# ClockGenerator.net
KiCad netlist of a schematic drawn in Altium Designer
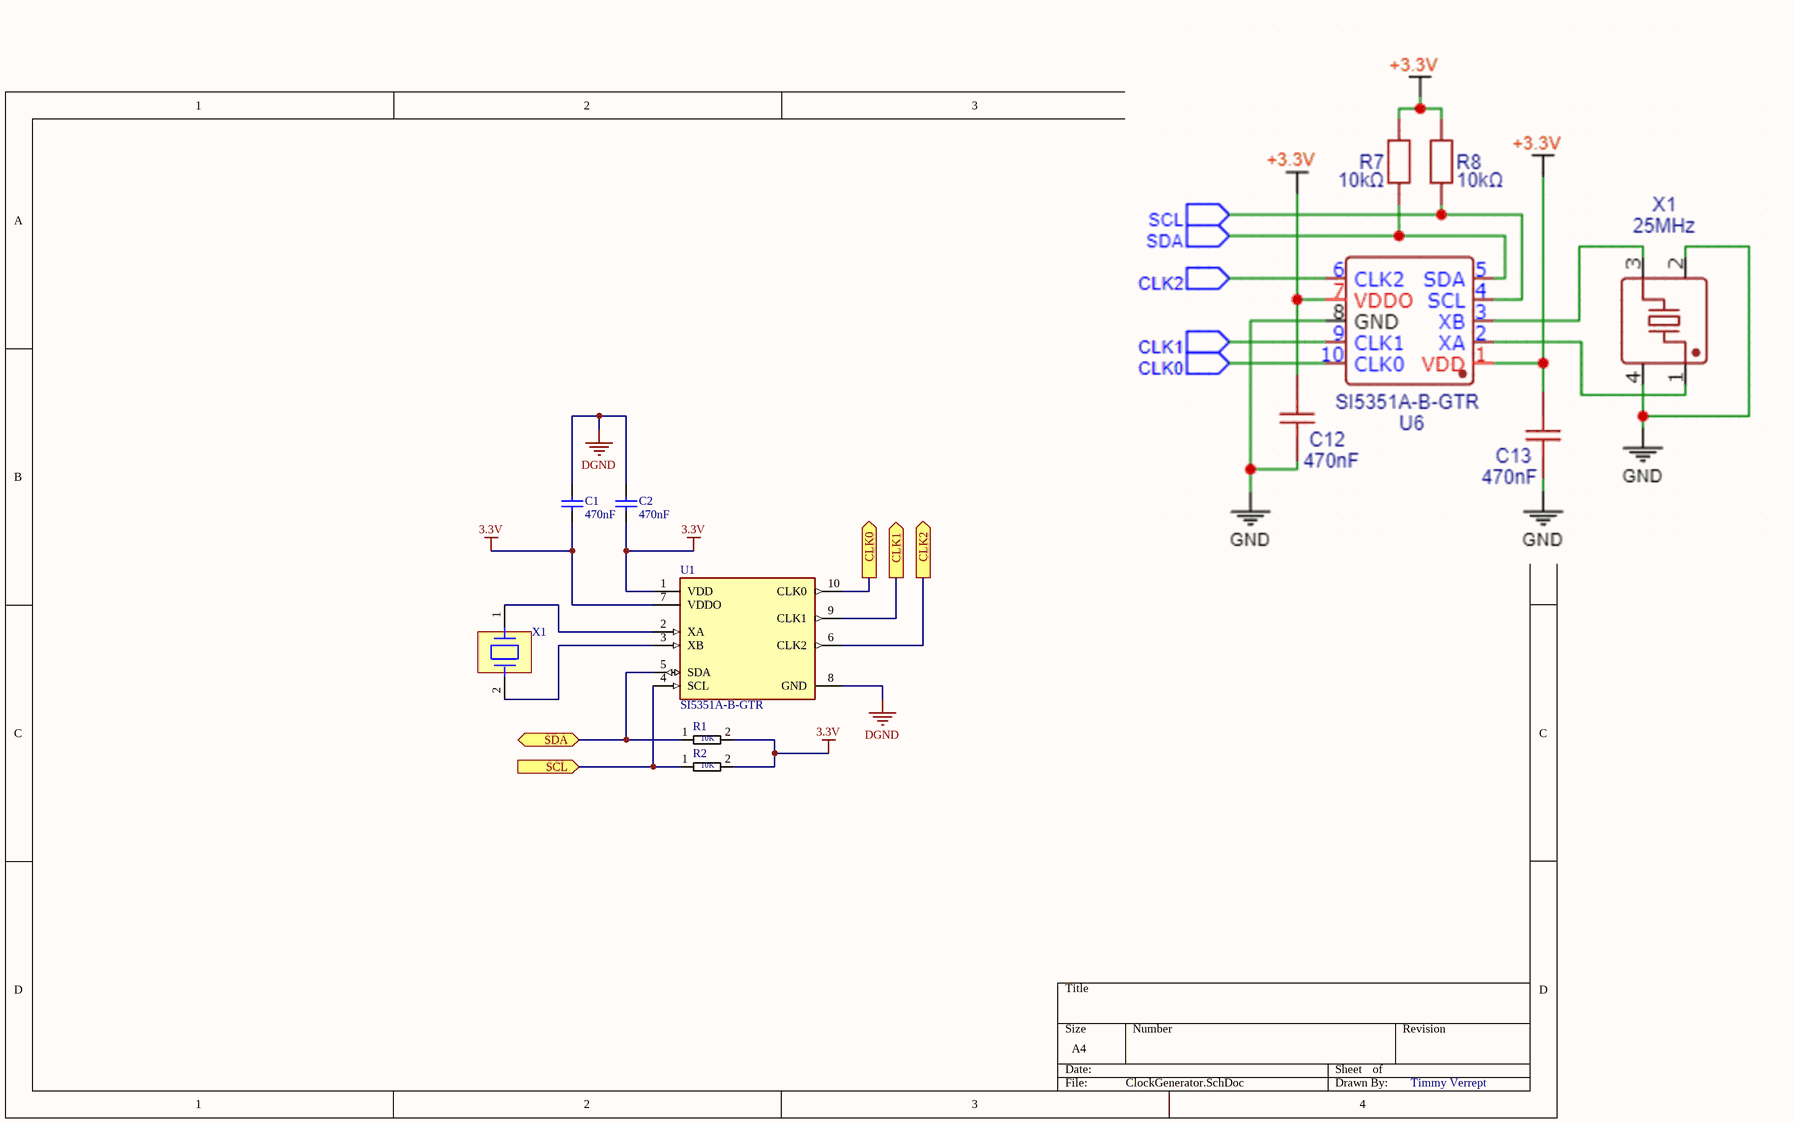
[diagram p0: ClockGenerator.SchDoc]

(export (version "E")
  (design (tool "Eeschema 10.0.6"))
  (components
    (comp (ref "C1")
      (value "470nF")
      (footprint "SMD_CAPACITOR")
      (fields (field (name "MANUFACTURER") "Vitramon") (field (name "PART NUMBER") "VJ0805Y682KXAMT"))
      (libsource (lib "Winnetrie_library") (part "CER Capacitor"))
    )
    (comp (ref "C2")
      (value "470nF")
      (footprint "SMD_CAPACITOR")
      (fields (field (name "MANUFACTURER") "Vitramon") (field (name "PART NUMBER") "VJ0805Y682KXAMT"))
      (libsource (lib "Winnetrie_library") (part "CER Capacitor"))
    )
    (comp (ref "R1")
      (value "10K")
      (footprint "SMD_RESISTOR")
      (description "RES SMD 681 OHM 0.1% 1/8W 0805")
      (fields
        (field (name "MANUFACTURER") "Yageo")
        (field (name "MANUFACTURER PART NUMBER") "RT0805BRD07681RL")
      )
      (libsource (lib "Winnetrie_library") (part "Resistor"))
    )
    (comp (ref "R2")
      (value "10K")
      (footprint "SMD_RESISTOR")
      (description "RES SMD 681 OHM 0.1% 1/8W 0805")
      (fields
        (field (name "MANUFACTURER") "Yageo")
        (field (name "MANUFACTURER PART NUMBER") "RT0805BRD07681RL")
      )
      (libsource (lib "Winnetrie_library") (part "Resistor"))
    )
    (comp (ref "U1")
      (value "SI5351A-B-GTR")
      (footprint "ClockGenerator")
      (description "IC CLK GENERATOR 200MHZ 10MSOP")
      (libsource (lib "Winnetrie_library") (part "Clock Generator"))
    )
    (comp (ref "X1")
      (value "ABM8W-25.0000MHZ-8-D1X-T3")
      (footprint "Crystal")
      (description "Crystal 25.0000Mhz 8Pf Smd Rohs Compliant: Yes ¦Abracon ABM8W-25.0000MHZ-8-D1X-T3")
      (fields
        (field (name "MOUSER PART NUMBER") "815-8W25-8D1XT")
        (field (name "DIGIKEY PART NUMBER") "535-14059-1-ND")
      )
      (libsource (lib "Winnetrie_library") (part "Crystal"))
    )
  )
  (nets
    (net (code "1") (name "/CLK0") (class "Default")
      (node (ref "U1") (pin "10") (pinfunction "CLK0_10") (pintype "output"))
    )
    (net (code "2") (name "/CLK1") (class "Default")
      (node (ref "U1") (pin "9") (pinfunction "CLK1_9") (pintype "output"))
    )
    (net (code "3") (name "/CLK2") (class "Default")
      (node (ref "U1") (pin "6") (pinfunction "CLK2_6") (pintype "output"))
    )
    (net (code "4") (name "/SCL") (class "Default")
      (node (ref "R2") (pin "1") (pinfunction "1_1") (pintype "passive"))
      (node (ref "U1") (pin "4") (pinfunction "SCL_4") (pintype "input"))
    )
    (net (code "5") (name "/SDA") (class "Default")
      (node (ref "R1") (pin "1") (pinfunction "1_1") (pintype "passive"))
      (node (ref "U1") (pin "5") (pinfunction "SDA_5") (pintype "bidirectional"))
    )
    (net (code "6") (name "3.3V") (class "Default")
      (node (ref "C1") (pin "1") (pinfunction "1_1") (pintype "passive"))
      (node (ref "C2") (pin "1") (pinfunction "1_1") (pintype "passive"))
      (node (ref "R1") (pin "2") (pinfunction "2_2") (pintype "passive"))
      (node (ref "R2") (pin "2") (pinfunction "2_2") (pintype "passive"))
      (node (ref "U1") (pin "1") (pinfunction "VDD_1") (pintype "power_in"))
      (node (ref "U1") (pin "7") (pinfunction "VDDO_7") (pintype "power_in"))
    )
    (net (code "7") (name "DGND") (class "Default")
      (node (ref "C1") (pin "2") (pinfunction "2_2") (pintype "passive"))
      (node (ref "C2") (pin "2") (pinfunction "2_2") (pintype "passive"))
      (node (ref "U1") (pin "8") (pinfunction "GND_8") (pintype "power_in"))
    )
    (net (code "8") (name "Net-(U1-XA)") (class "Default")
      (node (ref "U1") (pin "2") (pinfunction "XA_2") (pintype "input"))
      (node (ref "X1") (pin "1") (pinfunction "1_1") (pintype "passive"))
    )
    (net (code "9") (name "Net-(U1-XB)") (class "Default")
      (node (ref "U1") (pin "3") (pinfunction "XB_3") (pintype "input"))
      (node (ref "X1") (pin "2") (pinfunction "2_2") (pintype "passive"))
    )
  )
)
